# powerSupplyModule.net
KiCad netlist of a schematic drawn in EAGLE
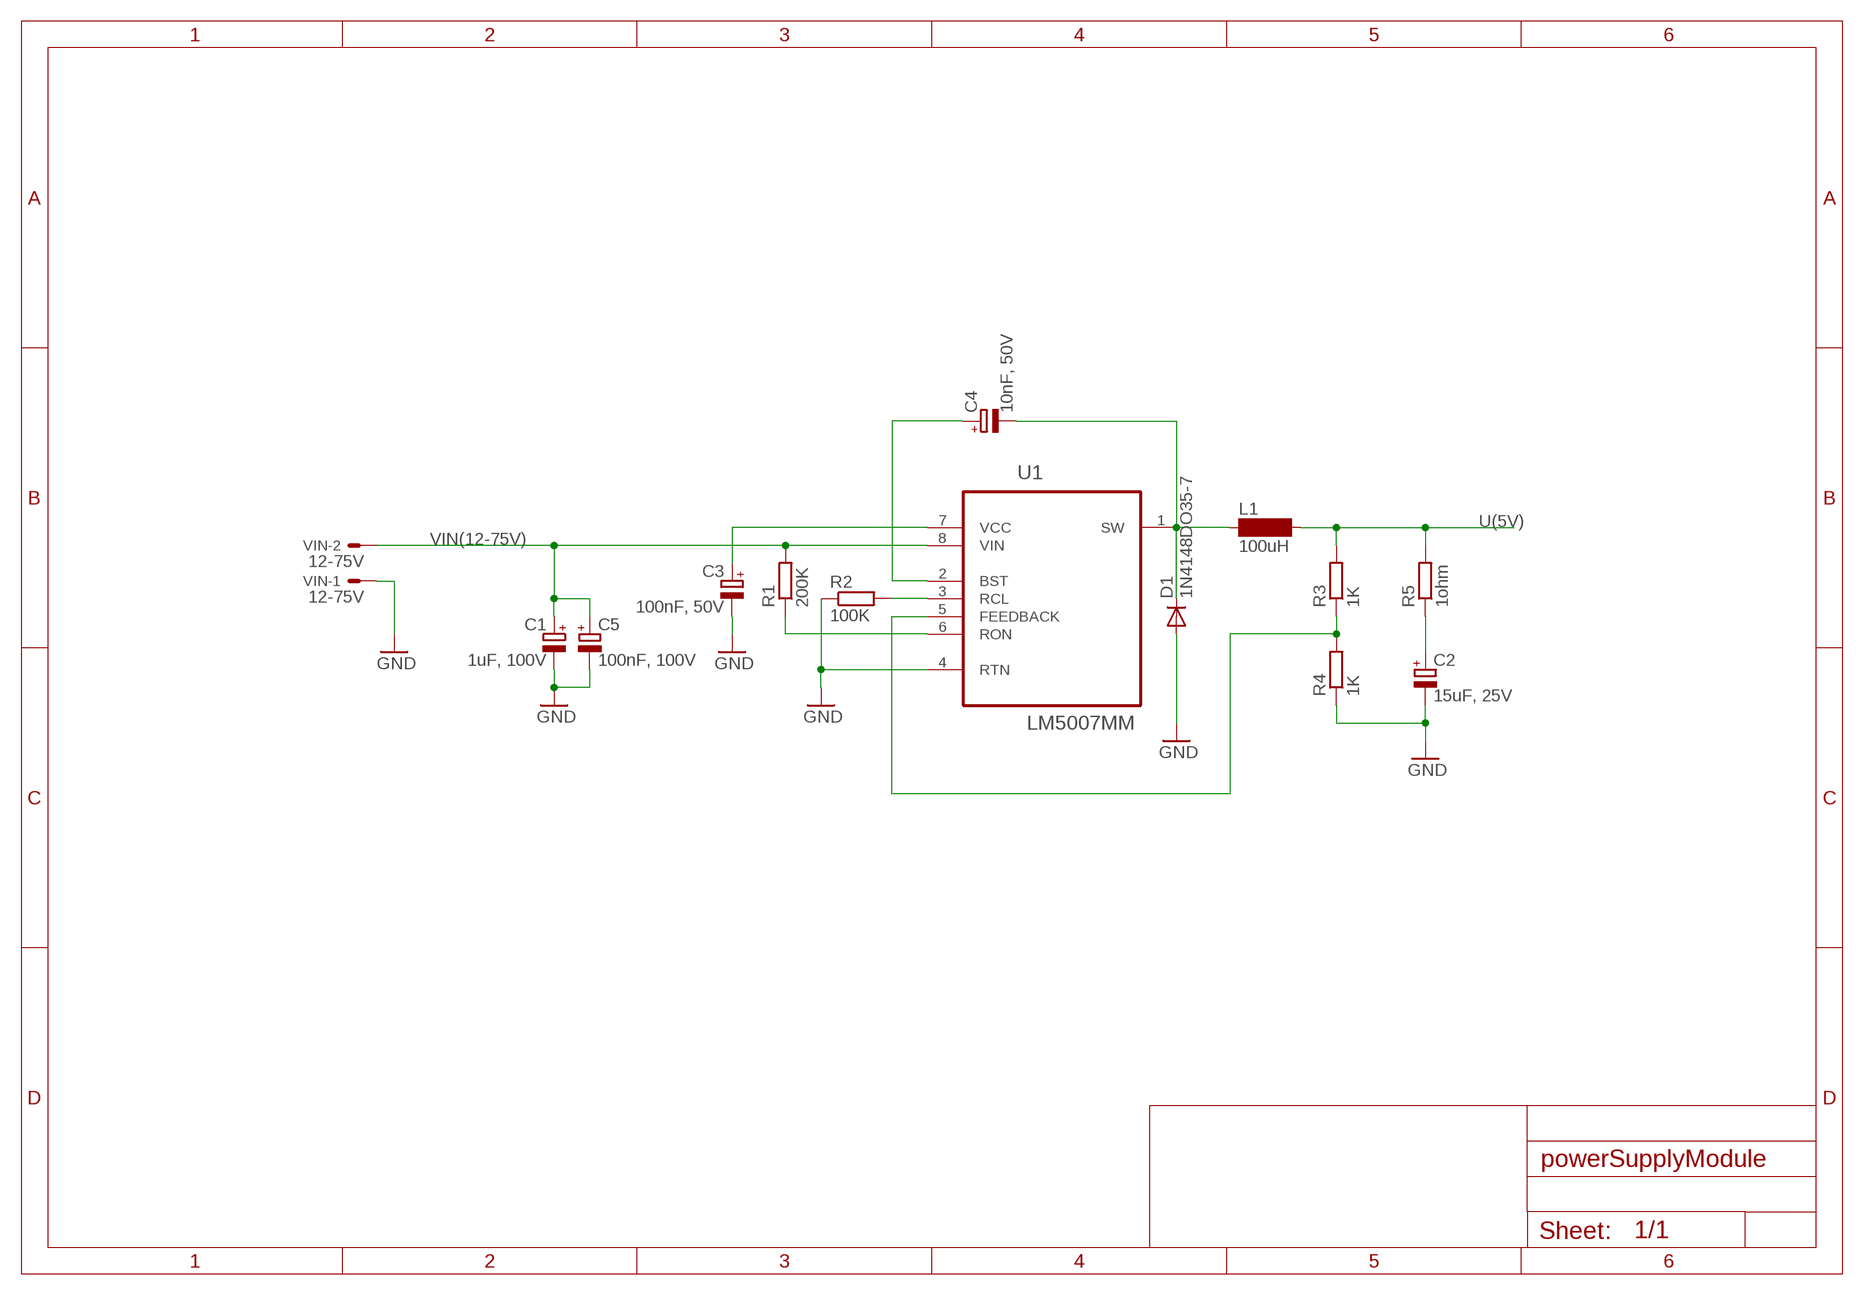
[diagram p0: schematic, sheet 1]

(export (version "E")
  (design (tool "Eeschema 10.0.6"))
  (components
    (comp (ref "C1")
      (value "1uF, 100V")
      (footprint "eagle-import:153CLV-0405")
      (libsource (lib "eagle-import") (part "CPOL-EU153CLV-0405"))
    )
    (comp (ref "C2")
      (value "15uF, 25V")
      (footprint "eagle-import:PANASONIC_C")
      (libsource (lib "eagle-import") (part "CPOL-EUC"))
    )
    (comp (ref "C3")
      (value "100nF, 50V")
      (footprint "eagle-import:SMC_A")
      (libsource (lib "eagle-import") (part "CPOL-EUSMCA"))
    )
    (comp (ref "C4")
      (value "10nF, 50V")
      (footprint "eagle-import:R_2012-12W")
      (libsource (lib "eagle-import") (part "CPOL-EUR/2012-12W"))
    )
    (comp (ref "C5")
      (value "100nF, 100V")
      (footprint "eagle-import:SMC_A")
      (libsource (lib "eagle-import") (part "CPOL-EUSMCA"))
    )
    (comp (ref "D1")
      (value "1N4148DO35-7")
      (footprint "eagle-import:DO35-7")
      (libsource (lib "eagle-import") (part "1N4148DO35-7"))
    )
    (comp (ref "L1")
      (value "100uH")
      (footprint "eagle-import:SM-Z15")
      (libsource (lib "eagle-import") (part "SM-Z15"))
    )
    (comp (ref "R1")
      (value "200K")
      (footprint "eagle-import:R2010")
      (libsource (lib "eagle-import") (part "R-EU_R2010"))
    )
    (comp (ref "R2")
      (value "100K")
      (footprint "eagle-import:R2010")
      (libsource (lib "eagle-import") (part "R-EU_R2010"))
    )
    (comp (ref "R3")
      (value "1K")
      (footprint "eagle-import:R2010")
      (libsource (lib "eagle-import") (part "R-EU_R2010"))
    )
    (comp (ref "R4")
      (value "1K")
      (footprint "eagle-import:R2010")
      (libsource (lib "eagle-import") (part "R-EU_R2010"))
    )
    (comp (ref "R5")
      (value "1ohm")
      (footprint "eagle-import:R2010")
      (libsource (lib "eagle-import") (part "R-EU_R2010"))
    )
    (comp (ref "U1")
      (value "LM5007MM")
      (footprint "eagle-import:SOP65P490X109-8N")
      (libsource (lib "eagle-import") (part "LM5007MM"))
    )
    (comp (ref "VIN")
      (value "12-75V")
      (footprint "eagle-import:5566-2")
      (libsource (lib "eagle-import") (part "5566-2"))
    )
  )
  (nets
    (net (code "1") (name "/U(5V)") (class "Default")
      (node (ref "L1") (pin "2") (pinfunction "2_2") (pintype "passive"))
      (node (ref "R3") (pin "2") (pinfunction "2_2") (pintype "passive"))
      (node (ref "R5") (pin "2") (pinfunction "2_2") (pintype "passive"))
    )
    (net (code "2") (name "/VIN(12-75V)") (class "Default")
      (node (ref "C1") (pin "+") (pinfunction "+_+") (pintype "passive"))
      (node (ref "C5") (pin "+") (pinfunction "+_+") (pintype "passive"))
      (node (ref "R1") (pin "2") (pinfunction "2_2") (pintype "passive"))
      (node (ref "U1") (pin "8") (pinfunction "VIN_8") (pintype "power_in"))
      (node (ref "VIN") (pin "2") (pinfunction "S_2") (pintype "passive"))
    )
    (net (code "3") (name "GND") (class "Default")
      (node (ref "C1") (pin "-") (pinfunction "-_-") (pintype "passive"))
      (node (ref "C2") (pin "-") (pinfunction "-_-") (pintype "passive"))
      (node (ref "C3") (pin "-") (pinfunction "-_-") (pintype "passive"))
      (node (ref "C5") (pin "-") (pinfunction "-_-") (pintype "passive"))
      (node (ref "D1") (pin "A") (pinfunction "A_A") (pintype "passive"))
      (node (ref "R2") (pin "1") (pinfunction "1_1") (pintype "passive"))
      (node (ref "R4") (pin "1") (pinfunction "1_1") (pintype "passive"))
      (node (ref "U1") (pin "4") (pinfunction "RTN_4") (pintype "passive"))
      (node (ref "VIN") (pin "1") (pinfunction "S_1") (pintype "passive"))
    )
    (net (code "4") (name "Net-(C2-Pad+)") (class "Default")
      (node (ref "C2") (pin "+") (pinfunction "+_+") (pintype "passive"))
      (node (ref "R5") (pin "1") (pinfunction "1_1") (pintype "passive"))
    )
    (net (code "5") (name "Net-(U1-BST)") (class "Default")
      (node (ref "C4") (pin "+") (pinfunction "+_+") (pintype "passive"))
      (node (ref "U1") (pin "2") (pinfunction "BST_2") (pintype "passive"))
    )
    (net (code "6") (name "Net-(U1-FEEDBACK)") (class "Default")
      (node (ref "R3") (pin "1") (pinfunction "1_1") (pintype "passive"))
      (node (ref "R4") (pin "2") (pinfunction "2_2") (pintype "passive"))
      (node (ref "U1") (pin "5") (pinfunction "FEEDBACK_5") (pintype "input"))
    )
    (net (code "7") (name "Net-(U1-RCL)") (class "Default")
      (node (ref "R2") (pin "2") (pinfunction "2_2") (pintype "passive"))
      (node (ref "U1") (pin "3") (pinfunction "RCL_3") (pintype "passive"))
    )
    (net (code "8") (name "Net-(U1-RON)") (class "Default")
      (node (ref "R1") (pin "1") (pinfunction "1_1") (pintype "passive"))
      (node (ref "U1") (pin "6") (pinfunction "RON_6") (pintype "input"))
    )
    (net (code "9") (name "Net-(U1-SW)") (class "Default")
      (node (ref "C4") (pin "-") (pinfunction "-_-") (pintype "passive"))
      (node (ref "D1") (pin "C") (pinfunction "C_C") (pintype "passive"))
      (node (ref "L1") (pin "1") (pinfunction "1_1") (pintype "passive"))
      (node (ref "U1") (pin "1") (pinfunction "SW_1") (pintype "output"))
    )
    (net (code "10") (name "Net-(U1-VCC)") (class "Default")
      (node (ref "C3") (pin "+") (pinfunction "+_+") (pintype "passive"))
      (node (ref "U1") (pin "7") (pinfunction "VCC_7") (pintype "power_in"))
    )
  )
)
